# Bike_sharing_system_final_one_with_30_pi.net
KiCad netlist of a schematic drawn in EasyEDA
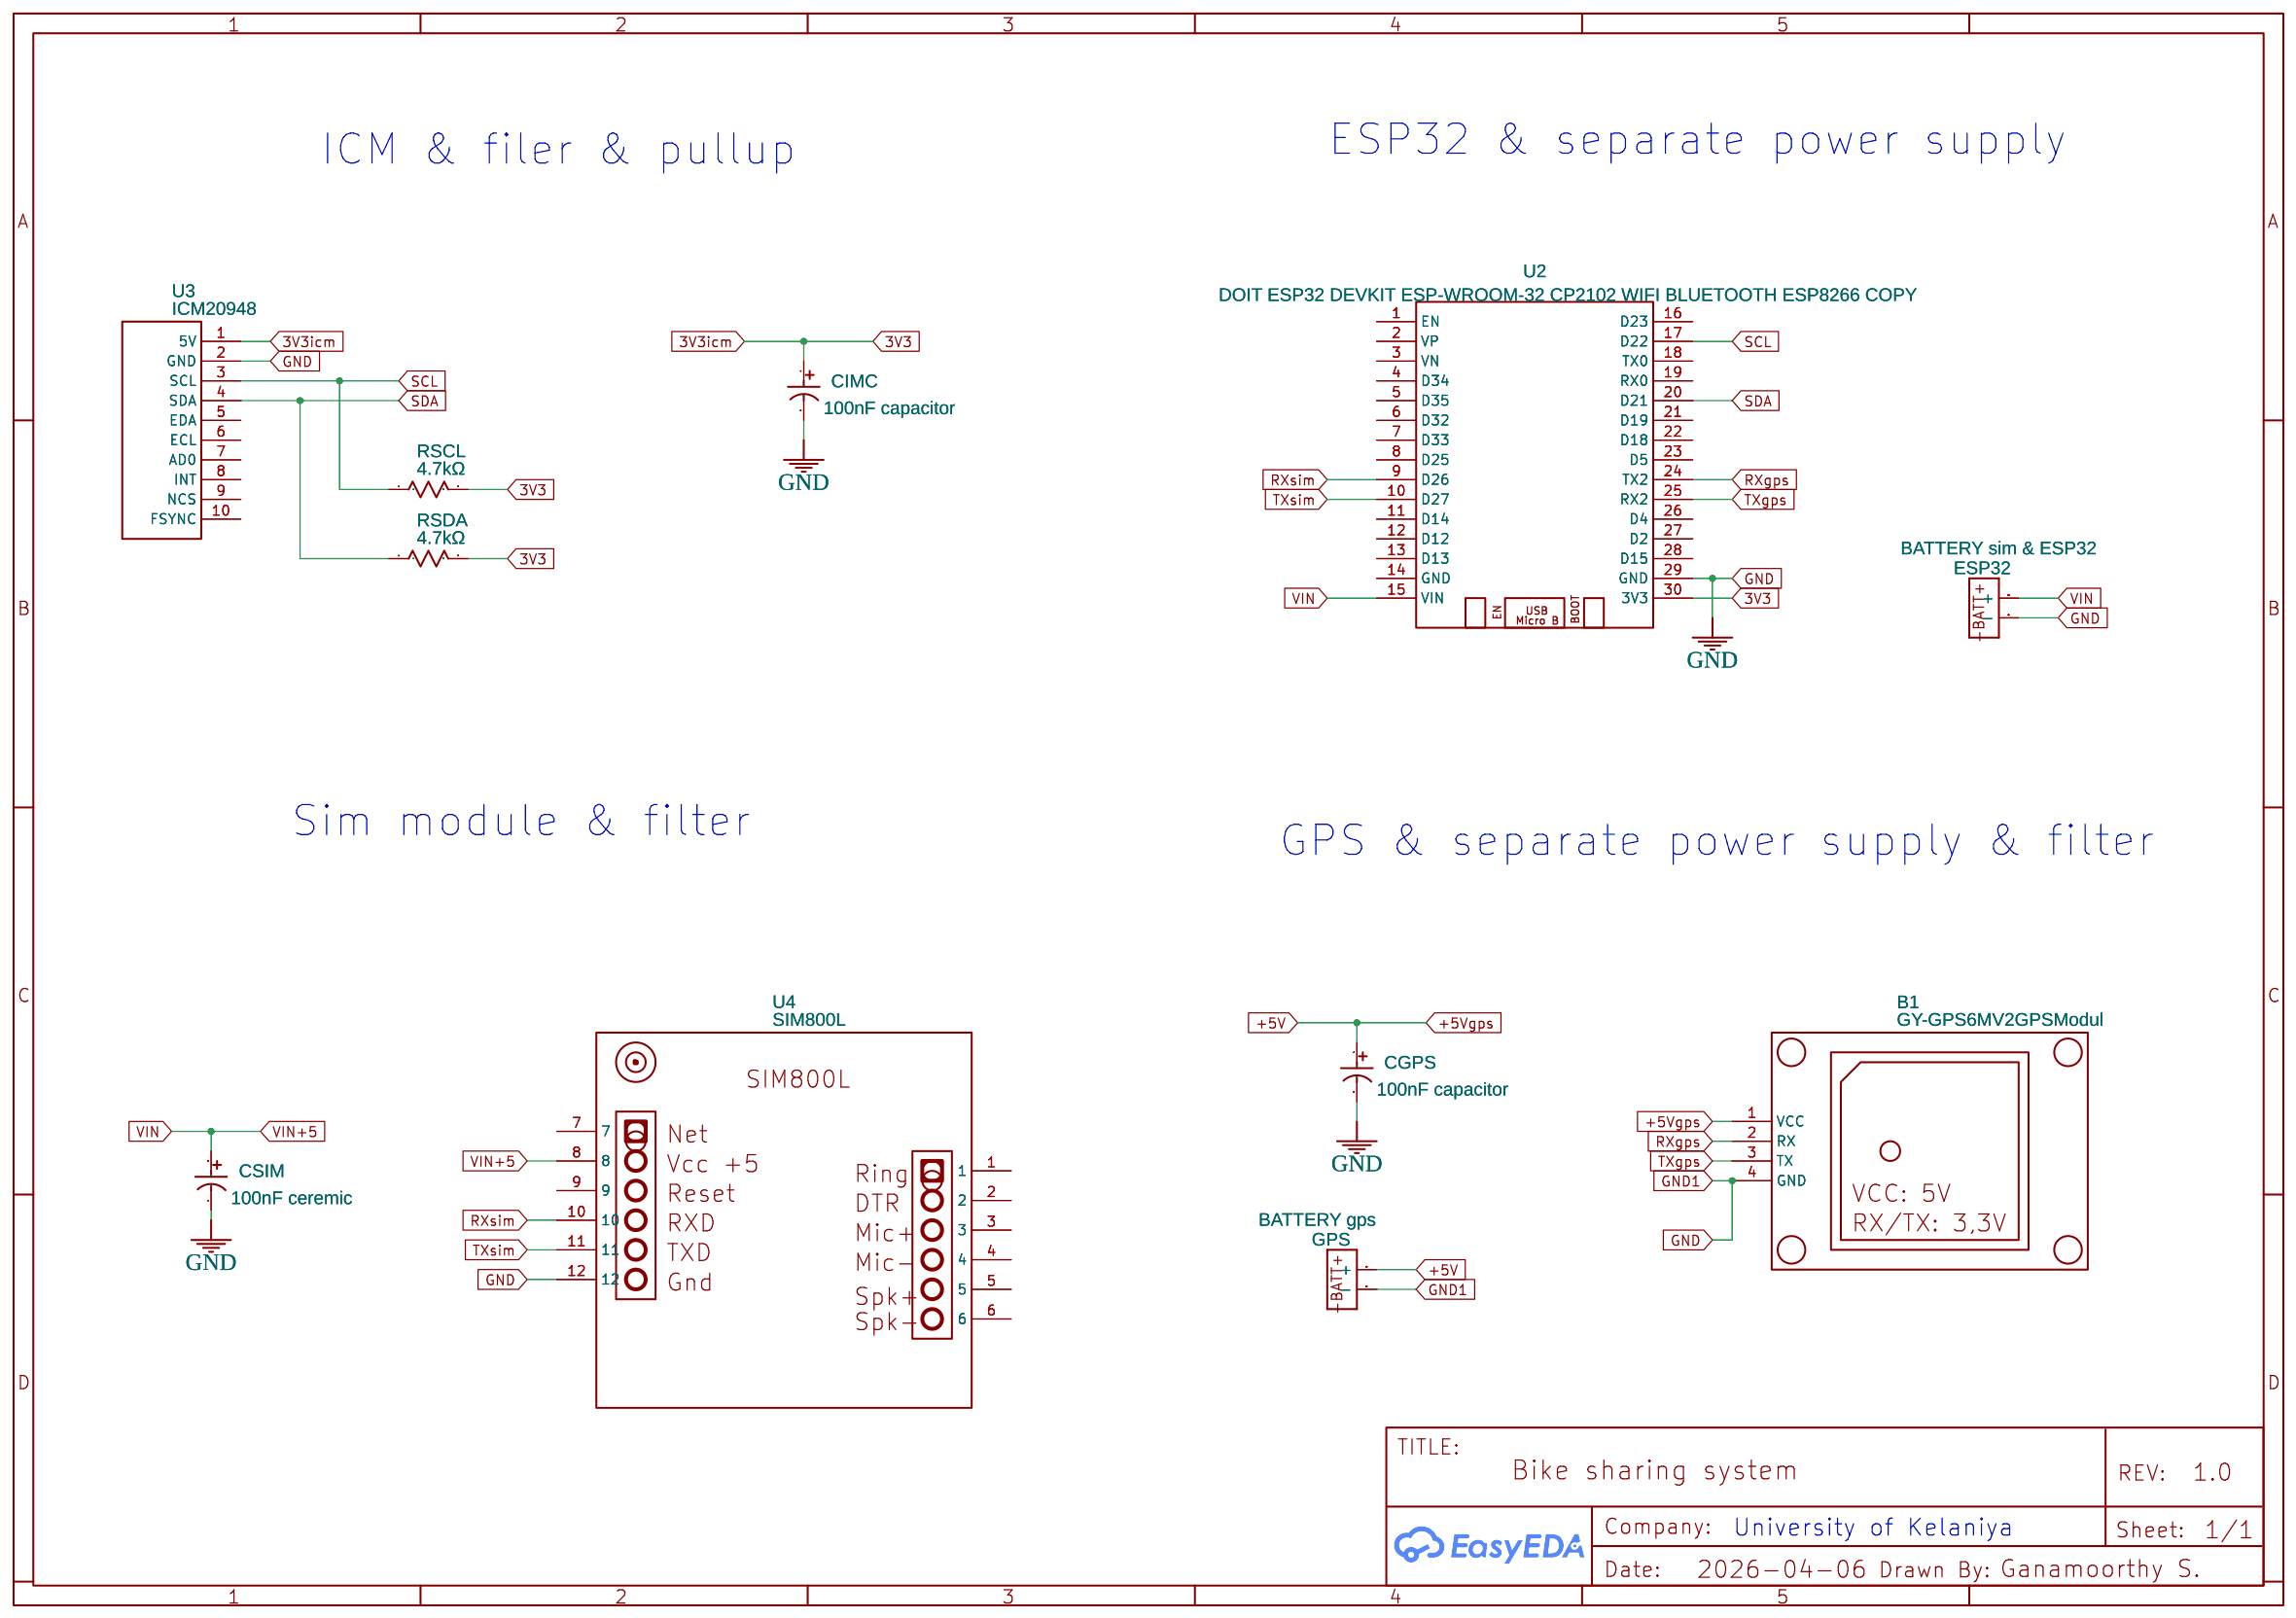
[diagram p0: schematic sheet]

(export (version "E")
  (design (tool "Eeschema 10.0.6"))
  (components
    (comp (ref "B1") (value "GY-GPS6MV2GPSModul") (libsource (lib "") (part "GY-GPS6MV2GPSModul")))
    (comp (ref "CGPS")
      (value "100nF capacitor")
      (fields
        (field (name "Manufacturer Part") "KM476M016D11RR0VH2FP0")
        (field (name "Manufacturer") "CX(承兴)")
      )
      (libsource (lib "") (part "CAPACITOR 680UF COPY"))
    )
    (comp (ref "CIMC")
      (value "100nF capacitor")
      (fields
        (field (name "Manufacturer Part") "KM476M016D11RR0VH2FP0")
        (field (name "Manufacturer") "CX(承兴)")
      )
      (libsource (lib "") (part "CAPACITOR 680UF COPY_1"))
    )
    (comp (ref "CSIM")
      (value "100nF ceremic")
      (fields
        (field (name "Manufacturer Part") "KM476M016D11RR0VH2FP0")
        (field (name "Manufacturer") "CX(承兴)")
      )
      (libsource (lib "") (part "CAPACITOR 680UF COPY_2"))
    )
    (comp (ref "ESP32") (value "BATTERY sim & ESP32") (libsource (lib "") (part "2 PIN CON (BATTERY)")))
    (comp (ref "GPS") (value "BATTERY gps") (libsource (lib "") (part "2 PIN CON (BATTERY)_1")))
    (comp (ref "RSCL")
      (value "4.7kΩ")
      (fields (field (name "Manufacturer Part") "Resister"))
      (libsource (lib "") (part "RESISTER COPY_1"))
    )
    (comp (ref "RSDA")
      (value "4.7kΩ")
      (fields (field (name "Manufacturer Part") "Resister"))
      (libsource (lib "") (part "RESISTER COPY"))
    )
    (comp (ref "U2")
      (value "DOIT ESP32 DEVKIT ESP-WROOM-32 CP2102 WIFI BLUETOOTH ESP8266 COPY")
      (libsource (lib "") (part "DOIT ESP32 DEVKIT ESP-WROOM-32 CP2102 WIFI BLUETOOTH ESP8266 COPY"))
    )
    (comp (ref "U3") (value "ICM20948") (libsource (lib "") (part "ICM20948")))
    (comp (ref "U4") (value "SIM800L") (libsource (lib "") (part "SIM800L")))
  )
  (nets
    (net (code "1") (name "+5V") (class "Default")
      (node (ref "B1") (pin "1") (pinfunction "VCC_1") (pintype "unspecified"))
      (node (ref "CGPS") (pin "1") (pinfunction "1_1") (pintype "unspecified"))
      (node (ref "GPS") (pin "BAT+") (pinfunction "+_BAT+") (pintype "unspecified"))
    )
    (net (code "2") (name "3V3") (class "Default")
      (node (ref "CIMC") (pin "1") (pinfunction "1_1") (pintype "unspecified"))
      (node (ref "RSCL") (pin "2") (pinfunction "2_2") (pintype "unspecified"))
      (node (ref "RSDA") (pin "2") (pinfunction "2_2") (pintype "unspecified"))
      (node (ref "U2") (pin "30") (pinfunction "3V3_30") (pintype "bidirectional"))
      (node (ref "U3") (pin "1") (pinfunction "5V_1") (pintype "unspecified"))
    )
    (net (code "3") (name "GND") (class "Default")
      (node (ref "B1") (pin "4") (pinfunction "GND_4") (pintype "unspecified"))
      (node (ref "CGPS") (pin "2") (pinfunction "2_2") (pintype "unspecified"))
      (node (ref "CIMC") (pin "2") (pinfunction "2_2") (pintype "unspecified"))
      (node (ref "CSIM") (pin "2") (pinfunction "2_2") (pintype "unspecified"))
      (node (ref "ESP32") (pin "BAT-") (pinfunction "-_BAT-") (pintype "unspecified"))
      (node (ref "GPS") (pin "BAT-") (pinfunction "-_BAT-") (pintype "unspecified"))
      (node (ref "U2") (pin "29") (pinfunction "GND_29") (pintype "bidirectional"))
      (node (ref "U3") (pin "2") (pinfunction "GND_2") (pintype "unspecified"))
      (node (ref "U4") (pin "12") (pinfunction "12_12") (pintype "unspecified"))
    )
    (net (code "4") (name "RXgps") (class "Default")
      (node (ref "B1") (pin "2") (pinfunction "RX_2") (pintype "unspecified"))
      (node (ref "U2") (pin "24") (pinfunction "TX2_24") (pintype "bidirectional"))
    )
    (net (code "5") (name "RXsim") (class "Default")
      (node (ref "U2") (pin "9") (pinfunction "D26_9") (pintype "bidirectional"))
      (node (ref "U4") (pin "10") (pinfunction "10_10") (pintype "unspecified"))
    )
    (net (code "6") (name "SCL") (class "Default")
      (node (ref "RSCL") (pin "1") (pinfunction "1_1") (pintype "unspecified"))
      (node (ref "U2") (pin "17") (pinfunction "D22_17") (pintype "bidirectional"))
      (node (ref "U3") (pin "3") (pinfunction "SCL_3") (pintype "unspecified"))
    )
    (net (code "7") (name "SDA") (class "Default")
      (node (ref "RSDA") (pin "1") (pinfunction "1_1") (pintype "unspecified"))
      (node (ref "U2") (pin "20") (pinfunction "D21_20") (pintype "bidirectional"))
      (node (ref "U3") (pin "4") (pinfunction "SDA_4") (pintype "unspecified"))
    )
    (net (code "8") (name "TXgps") (class "Default")
      (node (ref "B1") (pin "3") (pinfunction "TX_3") (pintype "unspecified"))
      (node (ref "U2") (pin "25") (pinfunction "RX2_25") (pintype "bidirectional"))
    )
    (net (code "9") (name "TXsim") (class "Default")
      (node (ref "U2") (pin "10") (pinfunction "D27_10") (pintype "bidirectional"))
      (node (ref "U4") (pin "11") (pinfunction "11_11") (pintype "unspecified"))
    )
    (net (code "10") (name "VIN") (class "Default")
      (node (ref "CSIM") (pin "1") (pinfunction "1_1") (pintype "unspecified"))
      (node (ref "ESP32") (pin "BAT+") (pinfunction "+_BAT+") (pintype "unspecified"))
      (node (ref "U2") (pin "15") (pinfunction "VIN_15") (pintype "input"))
      (node (ref "U4") (pin "8") (pinfunction "8_8") (pintype "unspecified"))
    )
    (net (code "11") (name "unconnected-(U2-D2-Pad27)") (class "Default")
      (node (ref "U2") (pin "27") (pinfunction "D2_27") (pintype "bidirectional"))
    )
    (net (code "12") (name "unconnected-(U2-D4-Pad26)") (class "Default")
      (node (ref "U2") (pin "26") (pinfunction "D4_26") (pintype "bidirectional"))
    )
    (net (code "13") (name "unconnected-(U2-D5-Pad23)") (class "Default")
      (node (ref "U2") (pin "23") (pinfunction "D5_23") (pintype "bidirectional"))
    )
    (net (code "14") (name "unconnected-(U2-D12-Pad12)") (class "Default")
      (node (ref "U2") (pin "12") (pinfunction "D12_12") (pintype "bidirectional"))
    )
    (net (code "15") (name "unconnected-(U2-D13-Pad13)") (class "Default")
      (node (ref "U2") (pin "13") (pinfunction "D13_13") (pintype "bidirectional"))
    )
    (net (code "16") (name "unconnected-(U2-D14-Pad11)") (class "Default")
      (node (ref "U2") (pin "11") (pinfunction "D14_11") (pintype "bidirectional"))
    )
    (net (code "17") (name "unconnected-(U2-D15-Pad28)") (class "Default")
      (node (ref "U2") (pin "28") (pinfunction "D15_28") (pintype "bidirectional"))
    )
    (net (code "18") (name "unconnected-(U2-D18-Pad22)") (class "Default")
      (node (ref "U2") (pin "22") (pinfunction "D18_22") (pintype "bidirectional"))
    )
    (net (code "19") (name "unconnected-(U2-D19-Pad21)") (class "Default")
      (node (ref "U2") (pin "21") (pinfunction "D19_21") (pintype "bidirectional"))
    )
    (net (code "20") (name "unconnected-(U2-D23-Pad16)") (class "Default")
      (node (ref "U2") (pin "16") (pinfunction "D23_16") (pintype "bidirectional"))
    )
    (net (code "21") (name "unconnected-(U2-D25-Pad8)") (class "Default")
      (node (ref "U2") (pin "8") (pinfunction "D25_8") (pintype "bidirectional"))
    )
    (net (code "22") (name "unconnected-(U2-D32-Pad6)") (class "Default")
      (node (ref "U2") (pin "6") (pinfunction "D32_6") (pintype "bidirectional"))
    )
    (net (code "23") (name "unconnected-(U2-D33-Pad7)") (class "Default")
      (node (ref "U2") (pin "7") (pinfunction "D33_7") (pintype "bidirectional"))
    )
    (net (code "24") (name "unconnected-(U2-D34-Pad4)") (class "Default")
      (node (ref "U2") (pin "4") (pinfunction "D34_4") (pintype "input"))
    )
    (net (code "25") (name "unconnected-(U2-D35-Pad5)") (class "Default")
      (node (ref "U2") (pin "5") (pinfunction "D35_5") (pintype "input"))
    )
    (net (code "26") (name "unconnected-(U2-EN-Pad1)") (class "Default")
      (node (ref "U2") (pin "1") (pinfunction "EN_1") (pintype "bidirectional"))
    )
    (net (code "27") (name "unconnected-(U2-GND-Pad14)") (class "Default")
      (node (ref "U2") (pin "14") (pinfunction "GND_14") (pintype "bidirectional"))
    )
    (net (code "28") (name "unconnected-(U2-RX0-Pad19)") (class "Default")
      (node (ref "U2") (pin "19") (pinfunction "RX0_19") (pintype "bidirectional"))
    )
    (net (code "29") (name "unconnected-(U2-TX0-Pad18)") (class "Default")
      (node (ref "U2") (pin "18") (pinfunction "TX0_18") (pintype "bidirectional"))
    )
    (net (code "30") (name "unconnected-(U2-VN-Pad3)") (class "Default")
      (node (ref "U2") (pin "3") (pinfunction "VN_3") (pintype "input"))
    )
    (net (code "31") (name "unconnected-(U2-VP-Pad2)") (class "Default")
      (node (ref "U2") (pin "2") (pinfunction "VP_2") (pintype "input"))
    )
    (net (code "32") (name "unconnected-(U3-AD0-Pad7)") (class "Default")
      (node (ref "U3") (pin "7") (pinfunction "AD0_7") (pintype "unspecified"))
    )
    (net (code "33") (name "unconnected-(U3-ECL-Pad6)") (class "Default")
      (node (ref "U3") (pin "6") (pinfunction "ECL_6") (pintype "unspecified"))
    )
    (net (code "34") (name "unconnected-(U3-EDA-Pad5)") (class "Default")
      (node (ref "U3") (pin "5") (pinfunction "EDA_5") (pintype "unspecified"))
    )
    (net (code "35") (name "unconnected-(U3-FSYNC-Pad10)") (class "Default")
      (node (ref "U3") (pin "10") (pinfunction "FSYNC_10") (pintype "unspecified"))
    )
    (net (code "36") (name "unconnected-(U3-INT-Pad8)") (class "Default")
      (node (ref "U3") (pin "8") (pinfunction "INT_8") (pintype "unspecified"))
    )
    (net (code "37") (name "unconnected-(U3-NCS-Pad9)") (class "Default")
      (node (ref "U3") (pin "9") (pinfunction "NCS_9") (pintype "unspecified"))
    )
    (net (code "38") (name "unconnected-(U4-Pad1)") (class "Default")
      (node (ref "U4") (pin "1") (pinfunction "1_1") (pintype "unspecified"))
    )
    (net (code "39") (name "unconnected-(U4-Pad2)") (class "Default")
      (node (ref "U4") (pin "2") (pinfunction "2_2") (pintype "unspecified"))
    )
    (net (code "40") (name "unconnected-(U4-Pad3)") (class "Default")
      (node (ref "U4") (pin "3") (pinfunction "3_3") (pintype "unspecified"))
    )
    (net (code "41") (name "unconnected-(U4-Pad4)") (class "Default")
      (node (ref "U4") (pin "4") (pinfunction "4_4") (pintype "unspecified"))
    )
    (net (code "42") (name "unconnected-(U4-Pad5)") (class "Default")
      (node (ref "U4") (pin "5") (pinfunction "5_5") (pintype "unspecified"))
    )
    (net (code "43") (name "unconnected-(U4-Pad6)") (class "Default")
      (node (ref "U4") (pin "6") (pinfunction "6_6") (pintype "unspecified"))
    )
    (net (code "44") (name "unconnected-(U4-Pad7)") (class "Default")
      (node (ref "U4") (pin "7") (pinfunction "7_7") (pintype "unspecified"))
    )
    (net (code "45") (name "unconnected-(U4-Pad9)") (class "Default")
      (node (ref "U4") (pin "9") (pinfunction "9_9") (pintype "unspecified"))
    )
  )
)
